# WMCB-V1.net
KiCad netlist of a schematic drawn in Altium Designer
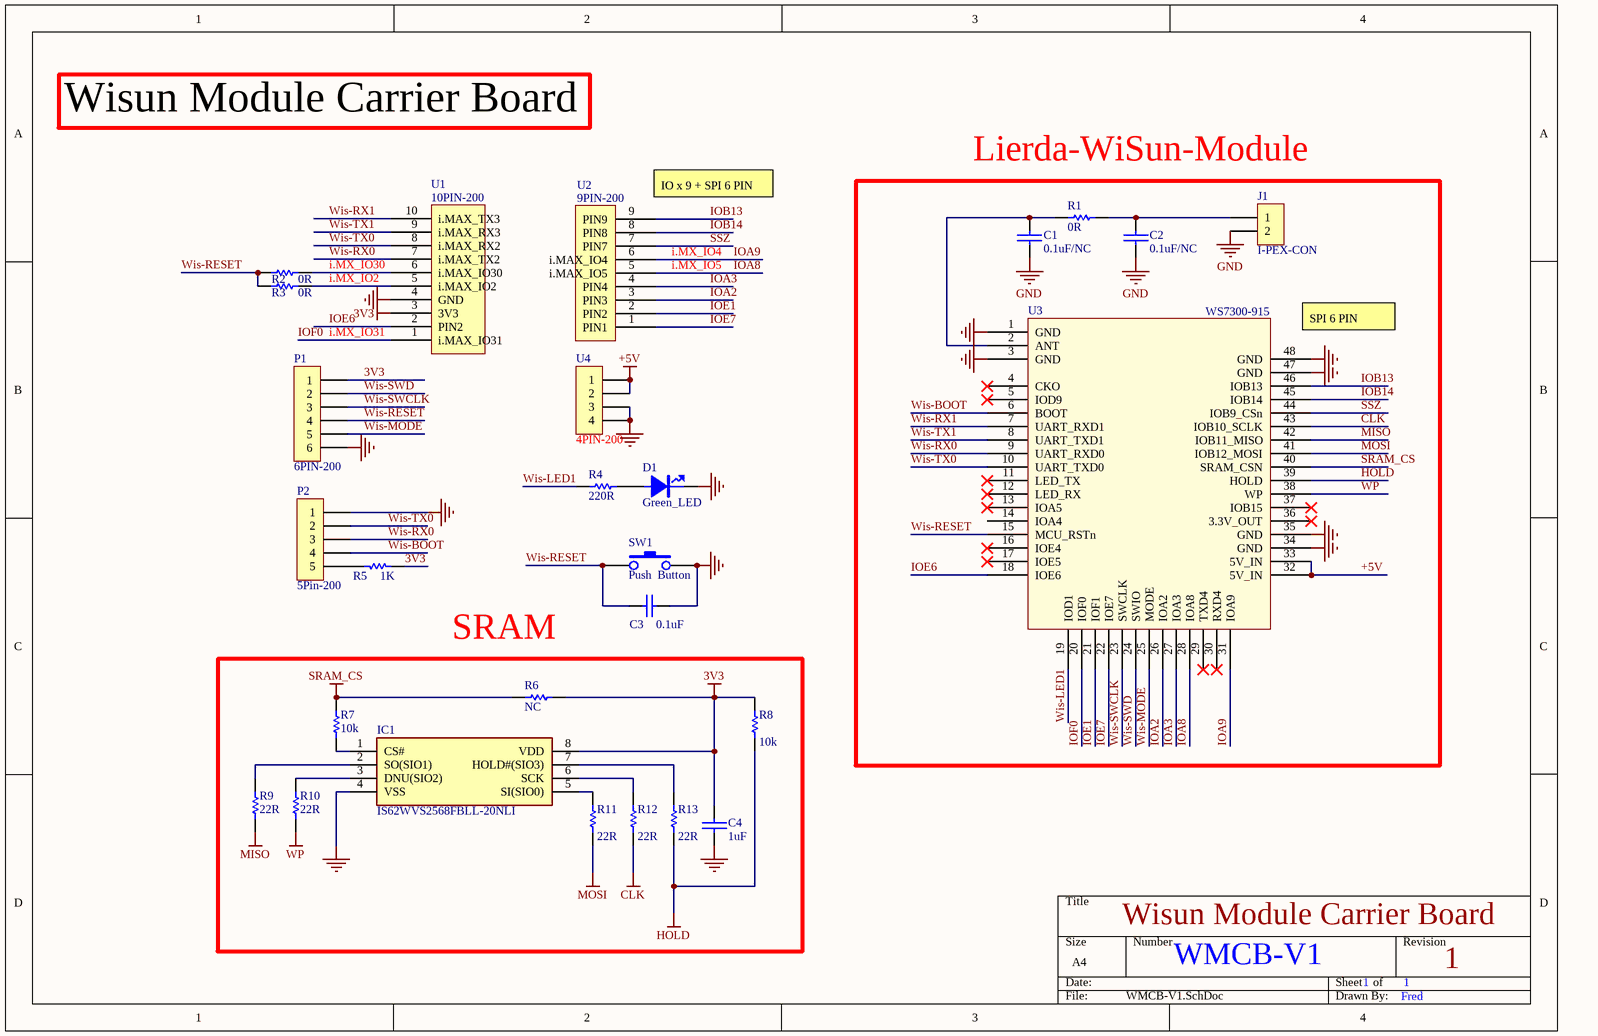
[diagram p0: WMCB-V1.SchDoc]

(export (version "E")
  (design (tool "Eeschema 10.0.6"))
  (components
    (comp (ref "C1")
      (value "0.1uF/NC")
      (footprint "0402C")
      (description "Capacitor")
      (libsource (lib "*") (part "CAP"))
    )
    (comp (ref "C2")
      (value "0.1uF/NC")
      (footprint "0402C")
      (description "Capacitor")
      (libsource (lib "*") (part "CAP"))
    )
    (comp (ref "C3")
      (value "0.1uF")
      (footprint "0402C")
      (description "Capacitor (Semiconductor SIM Model)")
      (fields (field (name "PUBLISHER") "Altium Limited"))
      (libsource (lib "*") (part "Cap Semi"))
    )
    (comp (ref "C4")
      (value "1uF")
      (footprint "0402C")
      (description "Capacitor")
      (libsource (lib "CAP") (part "CAP"))
    )
    (comp (ref "D1")
      (value "Green_LED")
      (footprint "LED0603--0.4mm")
      (fields
        (field (name "MANUFACTURER'S PART NUMBER") "CL-170G-CD-T")
        (field (name "PART NUMBER") "41100017000")
        (field (name "MANUFACTURER") "Citizen")
      )
      (libsource (lib "*") (part "LED"))
    )
    (comp (ref "IC1")
      (value "IS62WVS2568FBLL-20NLI")
      (footprint "SamacSys:SOIC127P600X175-8N")
      (description "Integrated Circuit")
      (fields (field (name "MOUSER2 PART NUMBER") "870-WVS2568FBLL20NLI"))
      (libsource (lib "*") (part "IS62WVS2568FBLL-20NLI"))
    )
    (comp (ref "J1")
      (value "I-PEX-CON")
      (footprint "I-PEX-CON")
      (description "Connector")
      (libsource (lib "*") (part "CON2"))
    )
    (comp (ref "P1")
      (value "6PIN-200")
      (footprint "6PIN-200")
      (description "Pin Header")
      (fields (field (name "PUBLISHER") "Altium Limited"))
      (libsource (lib "Miscellaneous Connectors") (part "6PIN-200"))
    )
    (comp (ref "P2") (value "5Pin-200") (footprint "5pin-200") (libsource (lib "PIN") (part "PIN5")))
    (comp (ref "R1")
      (value "0R")
      (footprint "0402")
      (description "Semiconductor Resistor")
      (fields (field (name "PUBLISHER") "Altium Limited"))
      (libsource (lib "*") (part "Res Semi"))
    )
    (comp (ref "R2")
      (value "0R")
      (footprint "0402")
      (description "Semiconductor Resistor")
      (fields (field (name "PUBLISHER") "Altium Limited"))
      (libsource (lib "*") (part "Res Semi"))
    )
    (comp (ref "R3")
      (value "0R")
      (footprint "0402")
      (description "Semiconductor Resistor")
      (fields (field (name "PUBLISHER") "Altium Limited"))
      (libsource (lib "*") (part "Res Semi"))
    )
    (comp (ref "R4")
      (value "220R")
      (footprint "0402")
      (description "Semiconductor Resistor")
      (fields (field (name "PUBLISHER") "Altium Limited"))
      (libsource (lib "*") (part "Res Semi"))
    )
    (comp (ref "R5")
      (value "1K")
      (footprint "0402")
      (description "Semiconductor Resistor")
      (fields (field (name "PUBLISHER") "Altium Limited"))
      (libsource (lib "*") (part "Res Semi"))
    )
    (comp (ref "R6")
      (value "NC")
      (footprint "0402")
      (description "Semiconductor Resistor")
      (fields (field (name "PUBLISHER") "Altium Limited"))
      (libsource (lib "*") (part "Res Semi"))
    )
    (comp (ref "R7")
      (value "10k")
      (footprint "0402")
      (description "Semiconductor Resistor")
      (fields (field (name "PUBLISHER") "Altium Limited"))
      (libsource (lib "*") (part "Res Semi"))
    )
    (comp (ref "R8")
      (value "10k")
      (footprint "0402")
      (description "Semiconductor Resistor")
      (fields (field (name "PUBLISHER") "Altium Limited"))
      (libsource (lib "*") (part "Res Semi"))
    )
    (comp (ref "R9")
      (value "22R")
      (footprint "0402")
      (description "Semiconductor Resistor")
      (fields (field (name "PUBLISHER") "Altium Limited"))
      (libsource (lib "*") (part "Res Semi"))
    )
    (comp (ref "R10")
      (value "22R")
      (footprint "0402")
      (description "Semiconductor Resistor")
      (fields (field (name "PUBLISHER") "Altium Limited"))
      (libsource (lib "*") (part "Res Semi"))
    )
    (comp (ref "R11")
      (value "22R")
      (footprint "0402")
      (description "Semiconductor Resistor")
      (fields (field (name "PUBLISHER") "Altium Limited"))
      (libsource (lib "*") (part "Res Semi"))
    )
    (comp (ref "R12")
      (value "22R")
      (footprint "0402")
      (description "Semiconductor Resistor")
      (fields (field (name "PUBLISHER") "Altium Limited"))
      (libsource (lib "*") (part "Res Semi"))
    )
    (comp (ref "R13")
      (value "22R")
      (footprint "0402")
      (description "Semiconductor Resistor")
      (fields (field (name "PUBLISHER") "Altium Limited"))
      (libsource (lib "*") (part "Res Semi"))
    )
    (comp (ref "SW1")
      (value "Push  Button")
      (footprint "Button_2pin-3*4*2MM")
      (description "Push Button")
      (libsource (lib "*") (part "SW1"))
    )
    (comp (ref "U1") (value "10PIN-200") (footprint "10PIN-200") (libsource (lib "*") (part "10PIN-200")))
    (comp (ref "U2") (value "9PIN-200") (footprint "9PIN-200") (libsource (lib "*") (part "9PIN-200")))
    (comp (ref "U3")
      (value "WS7300-915")
      (footprint "WS7300-915")
      (libsource (lib "MODULE") (part "WS7300-915"))
    )
    (comp (ref "U4")
      (value "4PIN-200")
      (footprint "4PIN-200")
      (description "Connector")
      (libsource (lib "*") (part "CON4"))
    )
  )
  (nets
    (net (code "1") (name "+5V") (class "Default")
      (node (ref "U3") (pin "32") (pinfunction "5V_IN_32") (pintype "passive"))
      (node (ref "U3") (pin "33") (pinfunction "5V_IN_33") (pintype "passive"))
      (node (ref "U4") (pin "1") (pinfunction "1_1") (pintype "passive"))
      (node (ref "U4") (pin "2") (pinfunction "2_2") (pintype "passive"))
    )
    (net (code "2") (name "/IOA2") (class "Default")
      (node (ref "U2") (pin "3") (pinfunction "PIN3_3") (pintype "passive"))
      (node (ref "U3") (pin "26") (pinfunction "IOA2_26") (pintype "passive"))
    )
    (net (code "3") (name "/IOA3") (class "Default")
      (node (ref "U2") (pin "4") (pinfunction "PIN4_4") (pintype "passive"))
      (node (ref "U3") (pin "27") (pinfunction "IOA3_27") (pintype "passive"))
    )
    (net (code "4") (name "/IOA8") (class "Default")
      (node (ref "U2") (pin "5") (pinfunction "i.MAX_IO5_5") (pintype "passive"))
      (node (ref "U3") (pin "28") (pinfunction "IOA8_28") (pintype "passive"))
    )
    (net (code "5") (name "/IOA9") (class "Default")
      (node (ref "U2") (pin "6") (pinfunction "i.MAX_IO4_6") (pintype "passive"))
      (node (ref "U3") (pin "31") (pinfunction "IOA9_31") (pintype "passive"))
    )
    (net (code "6") (name "/IOB13") (class "Default")
      (node (ref "U2") (pin "9") (pinfunction "PIN9_9") (pintype "passive"))
      (node (ref "U3") (pin "46") (pinfunction "IOB13_46") (pintype "passive"))
    )
    (net (code "7") (name "/IOB14") (class "Default")
      (node (ref "U2") (pin "8") (pinfunction "PIN8_8") (pintype "passive"))
      (node (ref "U3") (pin "45") (pinfunction "IOB14_45") (pintype "passive"))
    )
    (net (code "8") (name "/IOE1") (class "Default")
      (node (ref "U2") (pin "2") (pinfunction "PIN2_2") (pintype "passive"))
      (node (ref "U3") (pin "21") (pinfunction "IOF1_21") (pintype "passive"))
    )
    (net (code "9") (name "/IOE6") (class "Default")
      (node (ref "U1") (pin "2") (pinfunction "PIN2_2") (pintype "passive"))
      (node (ref "U3") (pin "18") (pinfunction "IOE6_18") (pintype "passive"))
    )
    (net (code "10") (name "/IOE7") (class "Default")
      (node (ref "U2") (pin "1") (pinfunction "PIN1_1") (pintype "passive"))
      (node (ref "U3") (pin "22") (pinfunction "IOE7_22") (pintype "passive"))
    )
    (net (code "11") (name "/IOF0") (class "Default")
      (node (ref "U1") (pin "1") (pinfunction "i.MAX_IO31_1") (pintype "passive"))
      (node (ref "U3") (pin "20") (pinfunction "IOF0_20") (pintype "passive"))
    )
    (net (code "12") (name "/SSZ") (class "Default")
      (node (ref "U2") (pin "7") (pinfunction "PIN7_7") (pintype "passive"))
      (node (ref "U3") (pin "44") (pinfunction "IOB9_CSn_44") (pintype "passive"))
    )
    (net (code "13") (name "/Wis-BOOT") (class "Default")
      (node (ref "P2") (pin "4") (pinfunction "4_4") (pintype "passive"))
      (node (ref "U3") (pin "6") (pinfunction "BOOT_6") (pintype "passive"))
    )
    (net (code "14") (name "/Wis-LED1") (class "Default")
      (node (ref "R4") (pin "2") (pinfunction "2_2") (pintype "passive"))
      (node (ref "U3") (pin "19") (pinfunction "IOD1_19") (pintype "passive"))
    )
    (net (code "15") (name "/Wis-MODE") (class "Default")
      (node (ref "P1") (pin "5") (pinfunction "5_5") (pintype "passive"))
      (node (ref "U3") (pin "25") (pinfunction "MODE_25") (pintype "passive"))
    )
    (net (code "16") (name "/Wis-RESET") (class "Default")
      (node (ref "C3") (pin "1") (pinfunction "1_1") (pintype "passive"))
      (node (ref "P1") (pin "4") (pinfunction "4_4") (pintype "passive"))
      (node (ref "R2") (pin "2") (pinfunction "2_2") (pintype "passive"))
      (node (ref "R3") (pin "2") (pinfunction "2_2") (pintype "passive"))
      (node (ref "SW1") (pin "1") (pinfunction "1_1") (pintype "passive"))
      (node (ref "U3") (pin "15") (pinfunction "MCU_RSTn_15") (pintype "passive"))
    )
    (net (code "17") (name "/Wis-RX0") (class "Default")
      (node (ref "P2") (pin "3") (pinfunction "3_3") (pintype "passive"))
      (node (ref "U1") (pin "7") (pinfunction "i.MAX_TX2_7") (pintype "passive"))
      (node (ref "U3") (pin "9") (pinfunction "UART_RXD0_9") (pintype "passive"))
    )
    (net (code "18") (name "/Wis-RX1") (class "Default")
      (node (ref "U1") (pin "10") (pinfunction "i.MAX_TX3_10") (pintype "passive"))
      (node (ref "U3") (pin "7") (pinfunction "UART_RXD1_7") (pintype "passive"))
    )
    (net (code "19") (name "/Wis-SWCLK") (class "Default")
      (node (ref "P1") (pin "3") (pinfunction "3_3") (pintype "passive"))
      (node (ref "U3") (pin "23") (pinfunction "SWCLK_23") (pintype "passive"))
    )
    (net (code "20") (name "/Wis-SWD") (class "Default")
      (node (ref "P1") (pin "2") (pinfunction "2_2") (pintype "passive"))
      (node (ref "U3") (pin "24") (pinfunction "SWIO_24") (pintype "passive"))
    )
    (net (code "21") (name "/Wis-TX0") (class "Default")
      (node (ref "P2") (pin "2") (pinfunction "2_2") (pintype "passive"))
      (node (ref "U1") (pin "8") (pinfunction "i.MAX_RX2_8") (pintype "passive"))
      (node (ref "U3") (pin "10") (pinfunction "UART_TXD0_10") (pintype "passive"))
    )
    (net (code "22") (name "/Wis-TX1") (class "Default")
      (node (ref "U1") (pin "9") (pinfunction "i.MAX_RX3_9") (pintype "passive"))
      (node (ref "U3") (pin "8") (pinfunction "UART_TXD1_8") (pintype "passive"))
    )
    (net (code "23") (name "/i.MX_IO2") (class "Default")
      (node (ref "R3") (pin "1") (pinfunction "1_1") (pintype "passive"))
      (node (ref "U1") (pin "5") (pinfunction "i.MAX_IO2_5") (pintype "passive"))
    )
    (net (code "24") (name "/i.MX_IO30") (class "Default")
      (node (ref "R2") (pin "1") (pinfunction "1_1") (pintype "passive"))
      (node (ref "U1") (pin "6") (pinfunction "i.MAX_IO30_6") (pintype "passive"))
    )
    (net (code "25") (name "3V3") (class "Default")
      (node (ref "C4") (pin "2") (pinfunction "2_2") (pintype "passive"))
      (node (ref "IC1") (pin "8") (pinfunction "VDD_8") (pintype "passive"))
      (node (ref "P1") (pin "1") (pinfunction "1_1") (pintype "passive"))
      (node (ref "R5") (pin "1") (pinfunction "1_1") (pintype "passive"))
      (node (ref "R6") (pin "1") (pinfunction "1_1") (pintype "passive"))
      (node (ref "R8") (pin "2") (pinfunction "2_2") (pintype "passive"))
      (node (ref "U1") (pin "3") (pinfunction "3V3_3") (pintype "passive"))
    )
    (net (code "26") (name "CLK") (class "Default")
      (node (ref "R12") (pin "1") (pinfunction "1_1") (pintype "passive"))
      (node (ref "U3") (pin "43") (pinfunction "IOB10_SCLK_43") (pintype "passive"))
    )
    (net (code "27") (name "GND") (class "Default")
      (node (ref "C1") (pin "1") (pinfunction "1_1") (pintype "passive"))
      (node (ref "C2") (pin "1") (pinfunction "1_1") (pintype "passive"))
      (node (ref "C3") (pin "2") (pinfunction "2_2") (pintype "passive"))
      (node (ref "C4") (pin "1") (pinfunction "1_1") (pintype "passive"))
      (node (ref "D1") (pin "2") (pinfunction "2_2") (pintype "passive"))
      (node (ref "IC1") (pin "4") (pinfunction "VSS_4") (pintype "passive"))
      (node (ref "J1") (pin "2") (pinfunction "2_2") (pintype "passive"))
      (node (ref "P1") (pin "6") (pinfunction "6_6") (pintype "passive"))
      (node (ref "P2") (pin "1") (pinfunction "1_1") (pintype "passive"))
      (node (ref "SW1") (pin "2") (pinfunction "2_2") (pintype "passive"))
      (node (ref "U1") (pin "4") (pinfunction "GND_4") (pintype "passive"))
      (node (ref "U3") (pin "1") (pinfunction "GND_1") (pintype "passive"))
      (node (ref "U3") (pin "3") (pinfunction "GND_3") (pintype "passive"))
      (node (ref "U3") (pin "34") (pinfunction "GND_34") (pintype "passive"))
      (node (ref "U3") (pin "35") (pinfunction "GND_35") (pintype "passive"))
      (node (ref "U3") (pin "47") (pinfunction "GND_47") (pintype "passive"))
      (node (ref "U3") (pin "48") (pinfunction "GND_48") (pintype "passive"))
      (node (ref "U4") (pin "3") (pinfunction "3_3") (pintype "passive"))
      (node (ref "U4") (pin "4") (pinfunction "4_4") (pintype "passive"))
    )
    (net (code "28") (name "HOLD") (class "Default")
      (node (ref "R13") (pin "1") (pinfunction "1_1") (pintype "passive"))
      (node (ref "R8") (pin "1") (pinfunction "1_1") (pintype "passive"))
      (node (ref "U3") (pin "39") (pinfunction "HOLD_39") (pintype "passive"))
    )
    (net (code "29") (name "MISO") (class "Default")
      (node (ref "R9") (pin "2") (pinfunction "2_2") (pintype "passive"))
      (node (ref "U3") (pin "42") (pinfunction "IOB11_MISO_42") (pintype "passive"))
    )
    (net (code "30") (name "MOSI") (class "Default")
      (node (ref "R11") (pin "1") (pinfunction "1_1") (pintype "passive"))
      (node (ref "U3") (pin "41") (pinfunction "IOB12_MOSI_41") (pintype "passive"))
    )
    (net (code "31") (name "Net-(C2-Pad2)") (class "Default")
      (node (ref "C2") (pin "2") (pinfunction "2_2") (pintype "passive"))
      (node (ref "J1") (pin "1") (pinfunction "1_1") (pintype "passive"))
      (node (ref "R1") (pin "2") (pinfunction "2_2") (pintype "passive"))
    )
    (net (code "32") (name "Net-(D1-Pad1)") (class "Default")
      (node (ref "D1") (pin "1") (pinfunction "1_1") (pintype "passive"))
      (node (ref "R4") (pin "1") (pinfunction "1_1") (pintype "passive"))
    )
    (net (code "33") (name "Net-(IC1-CS#)") (class "Default")
      (node (ref "IC1") (pin "1") (pinfunction "CS#_1") (pintype "passive"))
      (node (ref "R7") (pin "2") (pinfunction "2_2") (pintype "passive"))
    )
    (net (code "34") (name "Net-(IC1-DNU(SIO2))") (class "Default")
      (node (ref "IC1") (pin "3") (pinfunction "DNU(SIO2)_3") (pintype "passive"))
      (node (ref "R10") (pin "2") (pinfunction "2_2") (pintype "passive"))
    )
    (net (code "35") (name "Net-(IC1-HOLD#(SIO3))") (class "Default")
      (node (ref "IC1") (pin "7") (pinfunction "HOLD#(SIO3)_7") (pintype "passive"))
      (node (ref "R13") (pin "2") (pinfunction "2_2") (pintype "passive"))
    )
    (net (code "36") (name "Net-(IC1-SCK)") (class "Default")
      (node (ref "IC1") (pin "6") (pinfunction "SCK_6") (pintype "passive"))
      (node (ref "R12") (pin "2") (pinfunction "2_2") (pintype "passive"))
    )
    (net (code "37") (name "Net-(IC1-SI(SIO0))") (class "Default")
      (node (ref "IC1") (pin "5") (pinfunction "SI(SIO0)_5") (pintype "passive"))
      (node (ref "R11") (pin "2") (pinfunction "2_2") (pintype "passive"))
    )
    (net (code "38") (name "Net-(IC1-SO(SIO1))") (class "Default")
      (node (ref "IC1") (pin "2") (pinfunction "SO(SIO1)_2") (pintype "passive"))
      (node (ref "R9") (pin "1") (pinfunction "1_1") (pintype "passive"))
    )
    (net (code "39") (name "Net-(P2-Pad5)") (class "Default")
      (node (ref "P2") (pin "5") (pinfunction "5_5") (pintype "passive"))
      (node (ref "R5") (pin "2") (pinfunction "2_2") (pintype "passive"))
    )
    (net (code "40") (name "Net-(U3-ANT)") (class "Default")
      (node (ref "C1") (pin "2") (pinfunction "2_2") (pintype "passive"))
      (node (ref "R1") (pin "1") (pinfunction "1_1") (pintype "passive"))
      (node (ref "U3") (pin "2") (pinfunction "ANT_2") (pintype "passive"))
    )
    (net (code "41") (name "SRAM_CS") (class "Default")
      (node (ref "R6") (pin "2") (pinfunction "2_2") (pintype "passive"))
      (node (ref "R7") (pin "1") (pinfunction "1_1") (pintype "passive"))
      (node (ref "U3") (pin "40") (pinfunction "SRAM_CSN_40") (pintype "passive"))
    )
    (net (code "42") (name "WP") (class "Default")
      (node (ref "R10") (pin "1") (pinfunction "1_1") (pintype "passive"))
      (node (ref "U3") (pin "38") (pinfunction "WP_38") (pintype "passive"))
    )
    (net (code "43") (name "unconnected-(U3-3.3V_OUT-Pad36)") (class "Default")
      (node (ref "U3") (pin "36") (pinfunction "3.3V_OUT_36") (pintype "passive+no_connect"))
    )
    (net (code "44") (name "unconnected-(U3-CKO-Pad4)") (class "Default")
      (node (ref "U3") (pin "4") (pinfunction "CKO_4") (pintype "passive+no_connect"))
    )
    (net (code "45") (name "unconnected-(U3-IOA4-Pad14)") (class "Default")
      (node (ref "U3") (pin "14") (pinfunction "IOA4_14") (pintype "passive"))
    )
    (net (code "46") (name "unconnected-(U3-IOA5-Pad13)") (class "Default")
      (node (ref "U3") (pin "13") (pinfunction "IOA5_13") (pintype "passive+no_connect"))
    )
    (net (code "47") (name "unconnected-(U3-IOB15-Pad37)") (class "Default")
      (node (ref "U3") (pin "37") (pinfunction "IOB15_37") (pintype "passive+no_connect"))
    )
    (net (code "48") (name "unconnected-(U3-IOD9-Pad5)") (class "Default")
      (node (ref "U3") (pin "5") (pinfunction "IOD9_5") (pintype "passive+no_connect"))
    )
    (net (code "49") (name "unconnected-(U3-IOE4-Pad16)") (class "Default")
      (node (ref "U3") (pin "16") (pinfunction "IOE4_16") (pintype "passive+no_connect"))
    )
    (net (code "50") (name "unconnected-(U3-IOE5-Pad17)") (class "Default")
      (node (ref "U3") (pin "17") (pinfunction "IOE5_17") (pintype "passive+no_connect"))
    )
    (net (code "51") (name "unconnected-(U3-LED_RX-Pad12)") (class "Default")
      (node (ref "U3") (pin "12") (pinfunction "LED_RX_12") (pintype "passive+no_connect"))
    )
    (net (code "52") (name "unconnected-(U3-LED_TX-Pad11)") (class "Default")
      (node (ref "U3") (pin "11") (pinfunction "LED_TX_11") (pintype "passive+no_connect"))
    )
    (net (code "53") (name "unconnected-(U3-RXD4-Pad30)") (class "Default")
      (node (ref "U3") (pin "30") (pinfunction "RXD4_30") (pintype "passive+no_connect"))
    )
    (net (code "54") (name "unconnected-(U3-TXD4-Pad29)") (class "Default")
      (node (ref "U3") (pin "29") (pinfunction "TXD4_29") (pintype "passive+no_connect"))
    )
  )
)
